# mrf89_v1_0.net
KiCad netlist of a schematic drawn in EAGLE
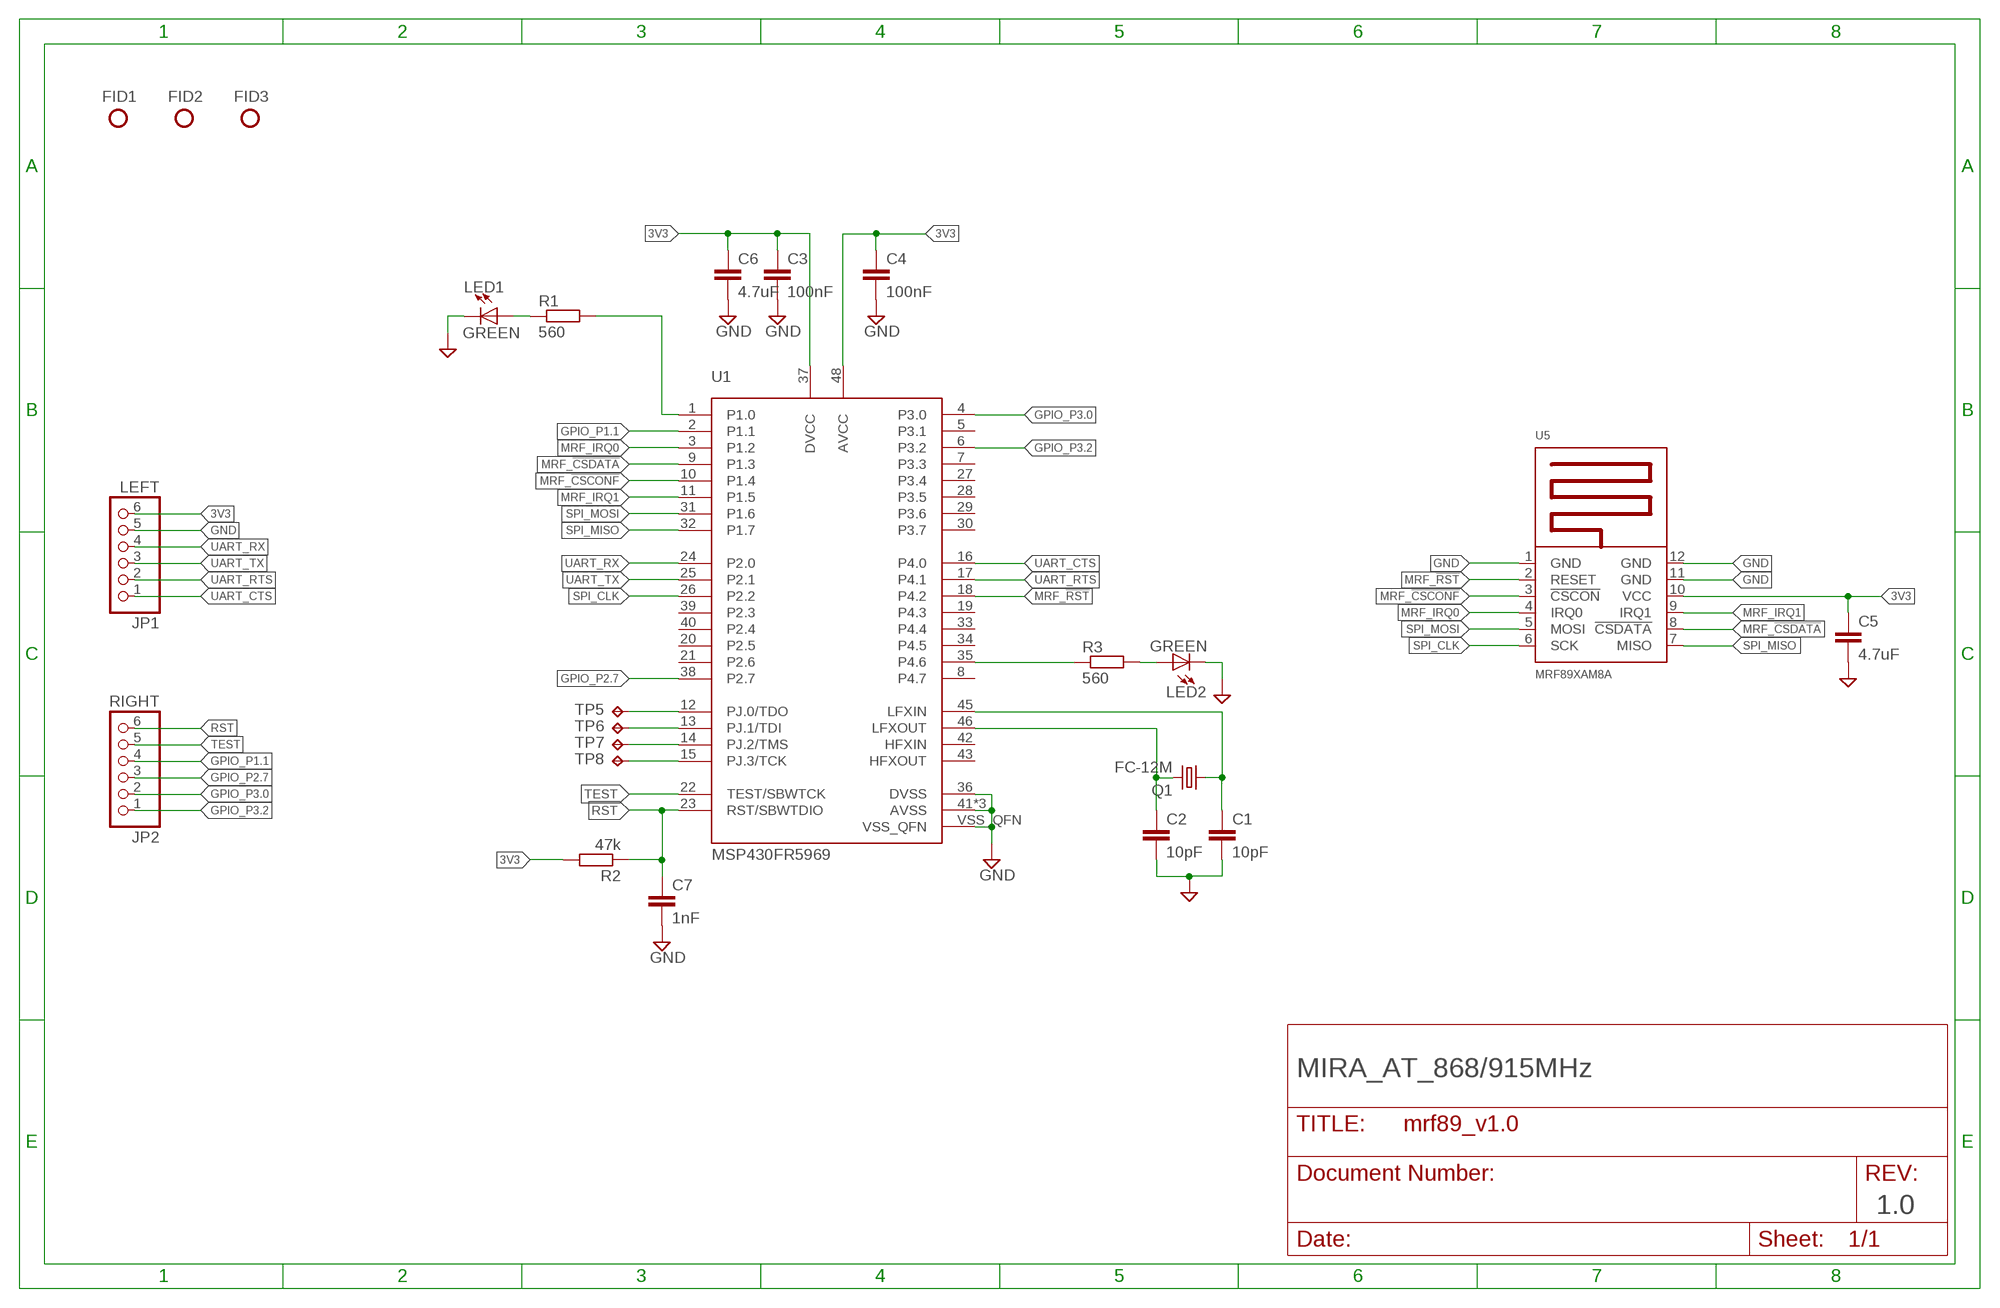
[diagram p0: schematic, sheet 1]

(export (version "E")
  (design (tool "Eeschema 10.0.6"))
  (components
    (comp (ref "C1")
      (value "10pF")
      (footprint "eagle-import:C0603")
      (libsource (lib "eagle-import") (part "C-EUC0603"))
    )
    (comp (ref "C2")
      (value "10pF")
      (footprint "eagle-import:C0603")
      (libsource (lib "eagle-import") (part "C-EUC0603"))
    )
    (comp (ref "C3")
      (value "100nF")
      (footprint "eagle-import:C0603")
      (libsource (lib "eagle-import") (part "C-EUC0603"))
    )
    (comp (ref "C4")
      (value "100nF")
      (footprint "eagle-import:C0603")
      (libsource (lib "eagle-import") (part "C-EUC0603"))
    )
    (comp (ref "C5")
      (value "4.7uF")
      (footprint "eagle-import:C0805")
      (libsource (lib "eagle-import") (part "C-EUC0805"))
    )
    (comp (ref "C6")
      (value "4.7uF")
      (footprint "eagle-import:C0805")
      (libsource (lib "eagle-import") (part "C-EUC0805"))
    )
    (comp (ref "C7")
      (value "1nF")
      (footprint "eagle-import:C0603")
      (libsource (lib "eagle-import") (part "C-EUC0603"))
    )
    (comp (ref "FID1")
      (value "FIDUCIAL")
      (footprint "eagle-import:FIDUCIAL")
      (libsource (lib "eagle-import") (part "FIDUCIAL"))
    )
    (comp (ref "FID2")
      (value "FIDUCIAL")
      (footprint "eagle-import:FIDUCIAL")
      (libsource (lib "eagle-import") (part "FIDUCIAL"))
    )
    (comp (ref "FID3")
      (value "FIDUCIAL")
      (footprint "eagle-import:FIDUCIAL")
      (libsource (lib "eagle-import") (part "FIDUCIAL"))
    )
    (comp (ref "JP1")
      (value "LEFT")
      (footprint "eagle-import:1X06")
      (libsource (lib "eagle-import") (part "PINHD-1X6"))
    )
    (comp (ref "JP2")
      (value "RIGHT")
      (footprint "eagle-import:1X06")
      (libsource (lib "eagle-import") (part "PINHD-1X6"))
    )
    (comp (ref "LED1")
      (value "GREEN")
      (footprint "eagle-import:CHIP-LED0603")
      (libsource (lib "eagle-import") (part "LEDCHIP-LED0603"))
    )
    (comp (ref "LED2")
      (value "GREEN")
      (footprint "eagle-import:CHIP-LED0603")
      (libsource (lib "eagle-import") (part "LEDCHIP-LED0603"))
    )
    (comp (ref "Q1")
      (value "FC-12M")
      (footprint "eagle-import:FC-12M")
      (libsource (lib "eagle-import") (part "FC-12M"))
    )
    (comp (ref "R1")
      (value "560")
      (footprint "eagle-import:R0603")
      (libsource (lib "eagle-import") (part "R-EU_R0603"))
    )
    (comp (ref "R2")
      (value "47k")
      (footprint "eagle-import:R0603")
      (libsource (lib "eagle-import") (part "R-EU_R0603"))
    )
    (comp (ref "R3")
      (value "560")
      (footprint "eagle-import:R0603")
      (libsource (lib "eagle-import") (part "R-EU_R0603"))
    )
    (comp (ref "TP5")
      (value "TPB1,27")
      (footprint "eagle-import:B1,27")
      (libsource (lib "eagle-import") (part "TPB1,27"))
    )
    (comp (ref "TP6")
      (value "TPB1,27")
      (footprint "eagle-import:B1,27")
      (libsource (lib "eagle-import") (part "TPB1,27"))
    )
    (comp (ref "TP7")
      (value "TPB1,27")
      (footprint "eagle-import:B1,27")
      (libsource (lib "eagle-import") (part "TPB1,27"))
    )
    (comp (ref "TP8")
      (value "TPB1,27")
      (footprint "eagle-import:B1,27")
      (libsource (lib "eagle-import") (part "TPB1,27"))
    )
    (comp (ref "U1")
      (value "MSP430FR5969")
      (footprint "eagle-import:S-PVQFN-N48")
      (libsource (lib "eagle-import") (part "MSP430FR5969"))
    )
    (comp (ref "U5")
      (value "MRF89XAM8A")
      (footprint "eagle-import:MRF89XAMXA")
      (libsource (lib "eagle-import") (part "MRF89XAM8A"))
    )
  )
  (nets
    (net (code "1") (name "/MRF_~{CSCONF}") (class "Default")
      (node (ref "U1") (pin "10") (pinfunction "P1.4_10") (pintype "bidirectional"))
      (node (ref "U5") (pin "3") (pinfunction "~{CSCON}_3") (pintype "input"))
    )
    (net (code "2") (name "/MRF_~{CSDATA}") (class "Default")
      (node (ref "U1") (pin "9") (pinfunction "P1.3_9") (pintype "bidirectional"))
      (node (ref "U5") (pin "8") (pinfunction "~{CSDATA}_8") (pintype "input"))
    )
    (net (code "3") (name "/MRF_~{RST}") (class "Default")
      (node (ref "U1") (pin "18") (pinfunction "P4.2_18") (pintype "bidirectional"))
      (node (ref "U5") (pin "2") (pinfunction "RESET_2") (pintype "input"))
    )
    (net (code "4") (name "3V3") (class "Default")
      (node (ref "C3") (pin "1") (pinfunction "1_1") (pintype "passive"))
      (node (ref "C4") (pin "1") (pinfunction "1_1") (pintype "passive"))
      (node (ref "C5") (pin "1") (pinfunction "1_1") (pintype "passive"))
      (node (ref "C6") (pin "1") (pinfunction "1_1") (pintype "passive"))
      (node (ref "JP1") (pin "6") (pinfunction "6_6") (pintype "passive"))
      (node (ref "R2") (pin "2") (pinfunction "2_2") (pintype "passive"))
      (node (ref "U1") (pin "37") (pinfunction "DVCC_37") (pintype "bidirectional"))
      (node (ref "U1") (pin "48") (pinfunction "AVCC_48") (pintype "bidirectional"))
      (node (ref "U5") (pin "10") (pinfunction "VCC_10") (pintype "power_in"))
    )
    (net (code "5") (name "GND") (class "Default")
      (node (ref "C1") (pin "2") (pinfunction "2_2") (pintype "passive"))
      (node (ref "C2") (pin "2") (pinfunction "2_2") (pintype "passive"))
      (node (ref "C3") (pin "2") (pinfunction "2_2") (pintype "passive"))
      (node (ref "C4") (pin "2") (pinfunction "2_2") (pintype "passive"))
      (node (ref "C5") (pin "2") (pinfunction "2_2") (pintype "passive"))
      (node (ref "C6") (pin "2") (pinfunction "2_2") (pintype "passive"))
      (node (ref "C7") (pin "2") (pinfunction "2_2") (pintype "passive"))
      (node (ref "JP1") (pin "5") (pinfunction "5_5") (pintype "passive"))
      (node (ref "LED1") (pin "C") (pinfunction "C_C") (pintype "passive"))
      (node (ref "LED2") (pin "C") (pinfunction "C_C") (pintype "passive"))
      (node (ref "U1") (pin "36") (pinfunction "DVSS_36") (pintype "bidirectional"))
      (node (ref "U1") (pin "41") (pinfunction "AVSS_41") (pintype "bidirectional"))
      (node (ref "U1") (pin "44") (pinfunction "AVSS_44") (pintype "bidirectional"))
      (node (ref "U1") (pin "47") (pinfunction "AVSS_47") (pintype "bidirectional"))
      (node (ref "U1") (pin "VSS_QFN") (pinfunction "VSS_QFN_VSS_QFN") (pintype "bidirectional"))
      (node (ref "U5") (pin "1") (pinfunction "GND_1") (pintype "power_in"))
      (node (ref "U5") (pin "11") (pinfunction "GND_11") (pintype "power_in"))
      (node (ref "U5") (pin "12") (pinfunction "GND_12") (pintype "power_in"))
    )
    (net (code "6") (name "GPIO_P1.1") (class "Default")
      (node (ref "JP2") (pin "4") (pinfunction "4_4") (pintype "passive"))
      (node (ref "U1") (pin "2") (pinfunction "P1.1_2") (pintype "bidirectional"))
    )
    (net (code "7") (name "GPIO_P2.7") (class "Default")
      (node (ref "JP2") (pin "3") (pinfunction "3_3") (pintype "passive"))
      (node (ref "U1") (pin "38") (pinfunction "P2.7_38") (pintype "bidirectional"))
    )
    (net (code "8") (name "GPIO_P3.0") (class "Default")
      (node (ref "JP2") (pin "2") (pinfunction "2_2") (pintype "passive"))
      (node (ref "U1") (pin "4") (pinfunction "P3.0_4") (pintype "bidirectional"))
    )
    (net (code "9") (name "GPIO_P3.2") (class "Default")
      (node (ref "JP2") (pin "1") (pinfunction "1_1") (pintype "passive"))
      (node (ref "U1") (pin "6") (pinfunction "P3.2_6") (pintype "bidirectional"))
    )
    (net (code "10") (name "MRF_IRQ0") (class "Default")
      (node (ref "U1") (pin "3") (pinfunction "P1.2_3") (pintype "bidirectional"))
      (node (ref "U5") (pin "4") (pinfunction "IRQ0_4") (pintype "output"))
    )
    (net (code "11") (name "MRF_IRQ1") (class "Default")
      (node (ref "U1") (pin "11") (pinfunction "P1.5_11") (pintype "bidirectional"))
      (node (ref "U5") (pin "9") (pinfunction "IRQ1_9") (pintype "output"))
    )
    (net (code "12") (name "Net-(LED1-PadA)") (class "Default")
      (node (ref "LED1") (pin "A") (pinfunction "A_A") (pintype "passive"))
      (node (ref "R1") (pin "1") (pinfunction "1_1") (pintype "passive"))
    )
    (net (code "13") (name "Net-(LED2-PadA)") (class "Default")
      (node (ref "LED2") (pin "A") (pinfunction "A_A") (pintype "passive"))
      (node (ref "R3") (pin "2") (pinfunction "2_2") (pintype "passive"))
    )
    (net (code "14") (name "Net-(U1-LFXIN)") (class "Default")
      (node (ref "C1") (pin "1") (pinfunction "1_1") (pintype "passive"))
      (node (ref "Q1") (pin "1") (pinfunction "1_1") (pintype "passive"))
      (node (ref "U1") (pin "45") (pinfunction "LFXIN_45") (pintype "bidirectional"))
    )
    (net (code "15") (name "Net-(U1-LFXOUT)") (class "Default")
      (node (ref "C2") (pin "1") (pinfunction "1_1") (pintype "passive"))
      (node (ref "Q1") (pin "2") (pinfunction "2_2") (pintype "passive"))
      (node (ref "U1") (pin "46") (pinfunction "LFXOUT_46") (pintype "bidirectional"))
    )
    (net (code "16") (name "Net-(U1-P1.0)") (class "Default")
      (node (ref "R1") (pin "2") (pinfunction "2_2") (pintype "passive"))
      (node (ref "U1") (pin "1") (pinfunction "P1.0_1") (pintype "bidirectional"))
    )
    (net (code "17") (name "Net-(U1-P4.6)") (class "Default")
      (node (ref "R3") (pin "1") (pinfunction "1_1") (pintype "passive"))
      (node (ref "U1") (pin "35") (pinfunction "P4.6_35") (pintype "bidirectional"))
    )
    (net (code "18") (name "Net-(U1-PJ.0{slash}TDO)") (class "Default")
      (node (ref "TP5") (pin "TP") (pinfunction "TP_TP") (pintype "input"))
      (node (ref "U1") (pin "12") (pinfunction "PJ.0/TDO_12") (pintype "bidirectional"))
    )
    (net (code "19") (name "Net-(U1-PJ.1{slash}TDI)") (class "Default")
      (node (ref "TP6") (pin "TP") (pinfunction "TP_TP") (pintype "input"))
      (node (ref "U1") (pin "13") (pinfunction "PJ.1/TDI_13") (pintype "bidirectional"))
    )
    (net (code "20") (name "Net-(U1-PJ.2{slash}TMS)") (class "Default")
      (node (ref "TP7") (pin "TP") (pinfunction "TP_TP") (pintype "input"))
      (node (ref "U1") (pin "14") (pinfunction "PJ.2/TMS_14") (pintype "bidirectional"))
    )
    (net (code "21") (name "Net-(U1-PJ.3{slash}TCK)") (class "Default")
      (node (ref "TP8") (pin "TP") (pinfunction "TP_TP") (pintype "input"))
      (node (ref "U1") (pin "15") (pinfunction "PJ.3/TCK_15") (pintype "bidirectional"))
    )
    (net (code "22") (name "RST") (class "Default")
      (node (ref "C7") (pin "1") (pinfunction "1_1") (pintype "passive"))
      (node (ref "JP2") (pin "6") (pinfunction "6_6") (pintype "passive"))
      (node (ref "R2") (pin "1") (pinfunction "1_1") (pintype "passive"))
      (node (ref "U1") (pin "23") (pinfunction "RST/SBWTDIO_23") (pintype "bidirectional"))
    )
    (net (code "23") (name "SPI_CLK") (class "Default")
      (node (ref "U1") (pin "26") (pinfunction "P2.2_26") (pintype "bidirectional"))
      (node (ref "U5") (pin "6") (pinfunction "SCK_6") (pintype "input"))
    )
    (net (code "24") (name "SPI_MISO") (class "Default")
      (node (ref "U1") (pin "32") (pinfunction "P1.7_32") (pintype "bidirectional"))
      (node (ref "U5") (pin "7") (pinfunction "MISO_7") (pintype "output"))
    )
    (net (code "25") (name "SPI_MOSI") (class "Default")
      (node (ref "U1") (pin "31") (pinfunction "P1.6_31") (pintype "bidirectional"))
      (node (ref "U5") (pin "5") (pinfunction "MOSI_5") (pintype "input"))
    )
    (net (code "26") (name "TEST") (class "Default")
      (node (ref "JP2") (pin "5") (pinfunction "5_5") (pintype "passive"))
      (node (ref "U1") (pin "22") (pinfunction "TEST/SBWTCK_22") (pintype "bidirectional"))
    )
    (net (code "27") (name "UART_CTS") (class "Default")
      (node (ref "JP1") (pin "1") (pinfunction "1_1") (pintype "passive"))
      (node (ref "U1") (pin "16") (pinfunction "P4.0_16") (pintype "bidirectional"))
    )
    (net (code "28") (name "UART_RTS") (class "Default")
      (node (ref "JP1") (pin "2") (pinfunction "2_2") (pintype "passive"))
      (node (ref "U1") (pin "17") (pinfunction "P4.1_17") (pintype "bidirectional"))
    )
    (net (code "29") (name "UART_RX") (class "Default")
      (node (ref "JP1") (pin "4") (pinfunction "4_4") (pintype "passive"))
      (node (ref "U1") (pin "24") (pinfunction "P2.0_24") (pintype "bidirectional"))
    )
    (net (code "30") (name "UART_TX") (class "Default")
      (node (ref "JP1") (pin "3") (pinfunction "3_3") (pintype "passive"))
      (node (ref "U1") (pin "25") (pinfunction "P2.1_25") (pintype "bidirectional"))
    )
    (net (code "31") (name "unconnected-(U1-HFXIN-Pad42)") (class "Default")
      (node (ref "U1") (pin "42") (pinfunction "HFXIN_42") (pintype "bidirectional"))
    )
    (net (code "32") (name "unconnected-(U1-HFXOUT-Pad43)") (class "Default")
      (node (ref "U1") (pin "43") (pinfunction "HFXOUT_43") (pintype "bidirectional"))
    )
    (net (code "33") (name "unconnected-(U1-P2.3-Pad39)") (class "Default")
      (node (ref "U1") (pin "39") (pinfunction "P2.3_39") (pintype "bidirectional"))
    )
    (net (code "34") (name "unconnected-(U1-P2.4-Pad40)") (class "Default")
      (node (ref "U1") (pin "40") (pinfunction "P2.4_40") (pintype "bidirectional"))
    )
    (net (code "35") (name "unconnected-(U1-P2.5-Pad20)") (class "Default")
      (node (ref "U1") (pin "20") (pinfunction "P2.5_20") (pintype "bidirectional"))
    )
    (net (code "36") (name "unconnected-(U1-P2.6-Pad21)") (class "Default")
      (node (ref "U1") (pin "21") (pinfunction "P2.6_21") (pintype "bidirectional"))
    )
    (net (code "37") (name "unconnected-(U1-P3.1-Pad5)") (class "Default")
      (node (ref "U1") (pin "5") (pinfunction "P3.1_5") (pintype "bidirectional"))
    )
    (net (code "38") (name "unconnected-(U1-P3.3-Pad7)") (class "Default")
      (node (ref "U1") (pin "7") (pinfunction "P3.3_7") (pintype "bidirectional"))
    )
    (net (code "39") (name "unconnected-(U1-P3.4-Pad27)") (class "Default")
      (node (ref "U1") (pin "27") (pinfunction "P3.4_27") (pintype "bidirectional"))
    )
    (net (code "40") (name "unconnected-(U1-P3.5-Pad28)") (class "Default")
      (node (ref "U1") (pin "28") (pinfunction "P3.5_28") (pintype "bidirectional"))
    )
    (net (code "41") (name "unconnected-(U1-P3.6-Pad29)") (class "Default")
      (node (ref "U1") (pin "29") (pinfunction "P3.6_29") (pintype "bidirectional"))
    )
    (net (code "42") (name "unconnected-(U1-P3.7-Pad30)") (class "Default")
      (node (ref "U1") (pin "30") (pinfunction "P3.7_30") (pintype "bidirectional"))
    )
    (net (code "43") (name "unconnected-(U1-P4.3-Pad19)") (class "Default")
      (node (ref "U1") (pin "19") (pinfunction "P4.3_19") (pintype "bidirectional"))
    )
    (net (code "44") (name "unconnected-(U1-P4.4-Pad33)") (class "Default")
      (node (ref "U1") (pin "33") (pinfunction "P4.4_33") (pintype "bidirectional"))
    )
    (net (code "45") (name "unconnected-(U1-P4.5-Pad34)") (class "Default")
      (node (ref "U1") (pin "34") (pinfunction "P4.5_34") (pintype "bidirectional"))
    )
    (net (code "46") (name "unconnected-(U1-P4.7-Pad8)") (class "Default")
      (node (ref "U1") (pin "8") (pinfunction "P4.7_8") (pintype "bidirectional"))
    )
  )
)
